# OXCLPC.net
KiCad netlist of a schematic drawn in EAGLE
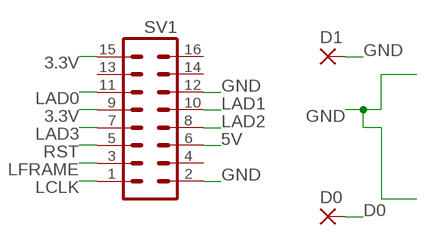
[diagram p0: schematic, sheet 1]

(export (version "E")
  (design (tool "Eeschema 10.0.6"))
  (components
    (comp (ref "D0")
      (value "SMD2")
      (footprint "eagle-import:SMD1,27-2,54")
      (libsource (lib "eagle-import") (part "SMD2"))
    )
    (comp (ref "D1")
      (value "SMD2")
      (footprint "eagle-import:SMD1,27-2,54")
      (libsource (lib "eagle-import") (part "SMD2"))
    )
    (comp (ref "SV1")
      (value "MA08-2")
      (footprint "eagle-import:MA08-2")
      (libsource (lib "eagle-import") (part "MA08-2"))
    )
  )
  (nets
    (net (code "1") (name "/3.3V") (class "Default")
      (node (ref "SV1") (pin "15") (pinfunction "15_15") (pintype "passive"))
      (node (ref "SV1") (pin "9") (pinfunction "9_9") (pintype "passive"))
    )
    (net (code "2") (name "/5V") (class "Default")
      (node (ref "SV1") (pin "6") (pinfunction "6_6") (pintype "passive"))
    )
    (net (code "3") (name "/D0") (class "Default")
      (node (ref "D0") (pin "1") (pinfunction "P_1") (pintype "passive"))
    )
    (net (code "4") (name "/GND") (class "Default")
      (node (ref "D1") (pin "1") (pinfunction "P_1") (pintype "passive"))
      (node (ref "SV1") (pin "12") (pinfunction "12_12") (pintype "passive"))
      (node (ref "SV1") (pin "2") (pinfunction "2_2") (pintype "passive"))
    )
    (net (code "5") (name "/LAD0") (class "Default")
      (node (ref "SV1") (pin "11") (pinfunction "11_11") (pintype "passive"))
    )
    (net (code "6") (name "/LAD1") (class "Default")
      (node (ref "SV1") (pin "10") (pinfunction "10_10") (pintype "passive"))
    )
    (net (code "7") (name "/LAD2") (class "Default")
      (node (ref "SV1") (pin "8") (pinfunction "8_8") (pintype "passive"))
    )
    (net (code "8") (name "/LAD3") (class "Default")
      (node (ref "SV1") (pin "7") (pinfunction "7_7") (pintype "passive"))
    )
    (net (code "9") (name "/LCLK") (class "Default")
      (node (ref "SV1") (pin "1") (pinfunction "1_1") (pintype "passive"))
    )
    (net (code "10") (name "/LFRAME") (class "Default")
      (node (ref "SV1") (pin "3") (pinfunction "3_3") (pintype "passive"))
    )
    (net (code "11") (name "/RST") (class "Default")
      (node (ref "SV1") (pin "5") (pinfunction "5_5") (pintype "passive"))
    )
    (net (code "12") (name "unconnected-(SV1-Pad4)") (class "Default")
      (node (ref "SV1") (pin "4") (pinfunction "4_4") (pintype "passive"))
    )
    (net (code "13") (name "unconnected-(SV1-Pad13)") (class "Default")
      (node (ref "SV1") (pin "13") (pinfunction "13_13") (pintype "passive"))
    )
    (net (code "14") (name "unconnected-(SV1-Pad14)") (class "Default")
      (node (ref "SV1") (pin "14") (pinfunction "14_14") (pintype "passive"))
    )
    (net (code "15") (name "unconnected-(SV1-Pad16)") (class "Default")
      (node (ref "SV1") (pin "16") (pinfunction "16_16") (pintype "passive"))
    )
  )
)
